# NoteRF_0_3.net
KiCad netlist of a schematic drawn in EAGLE
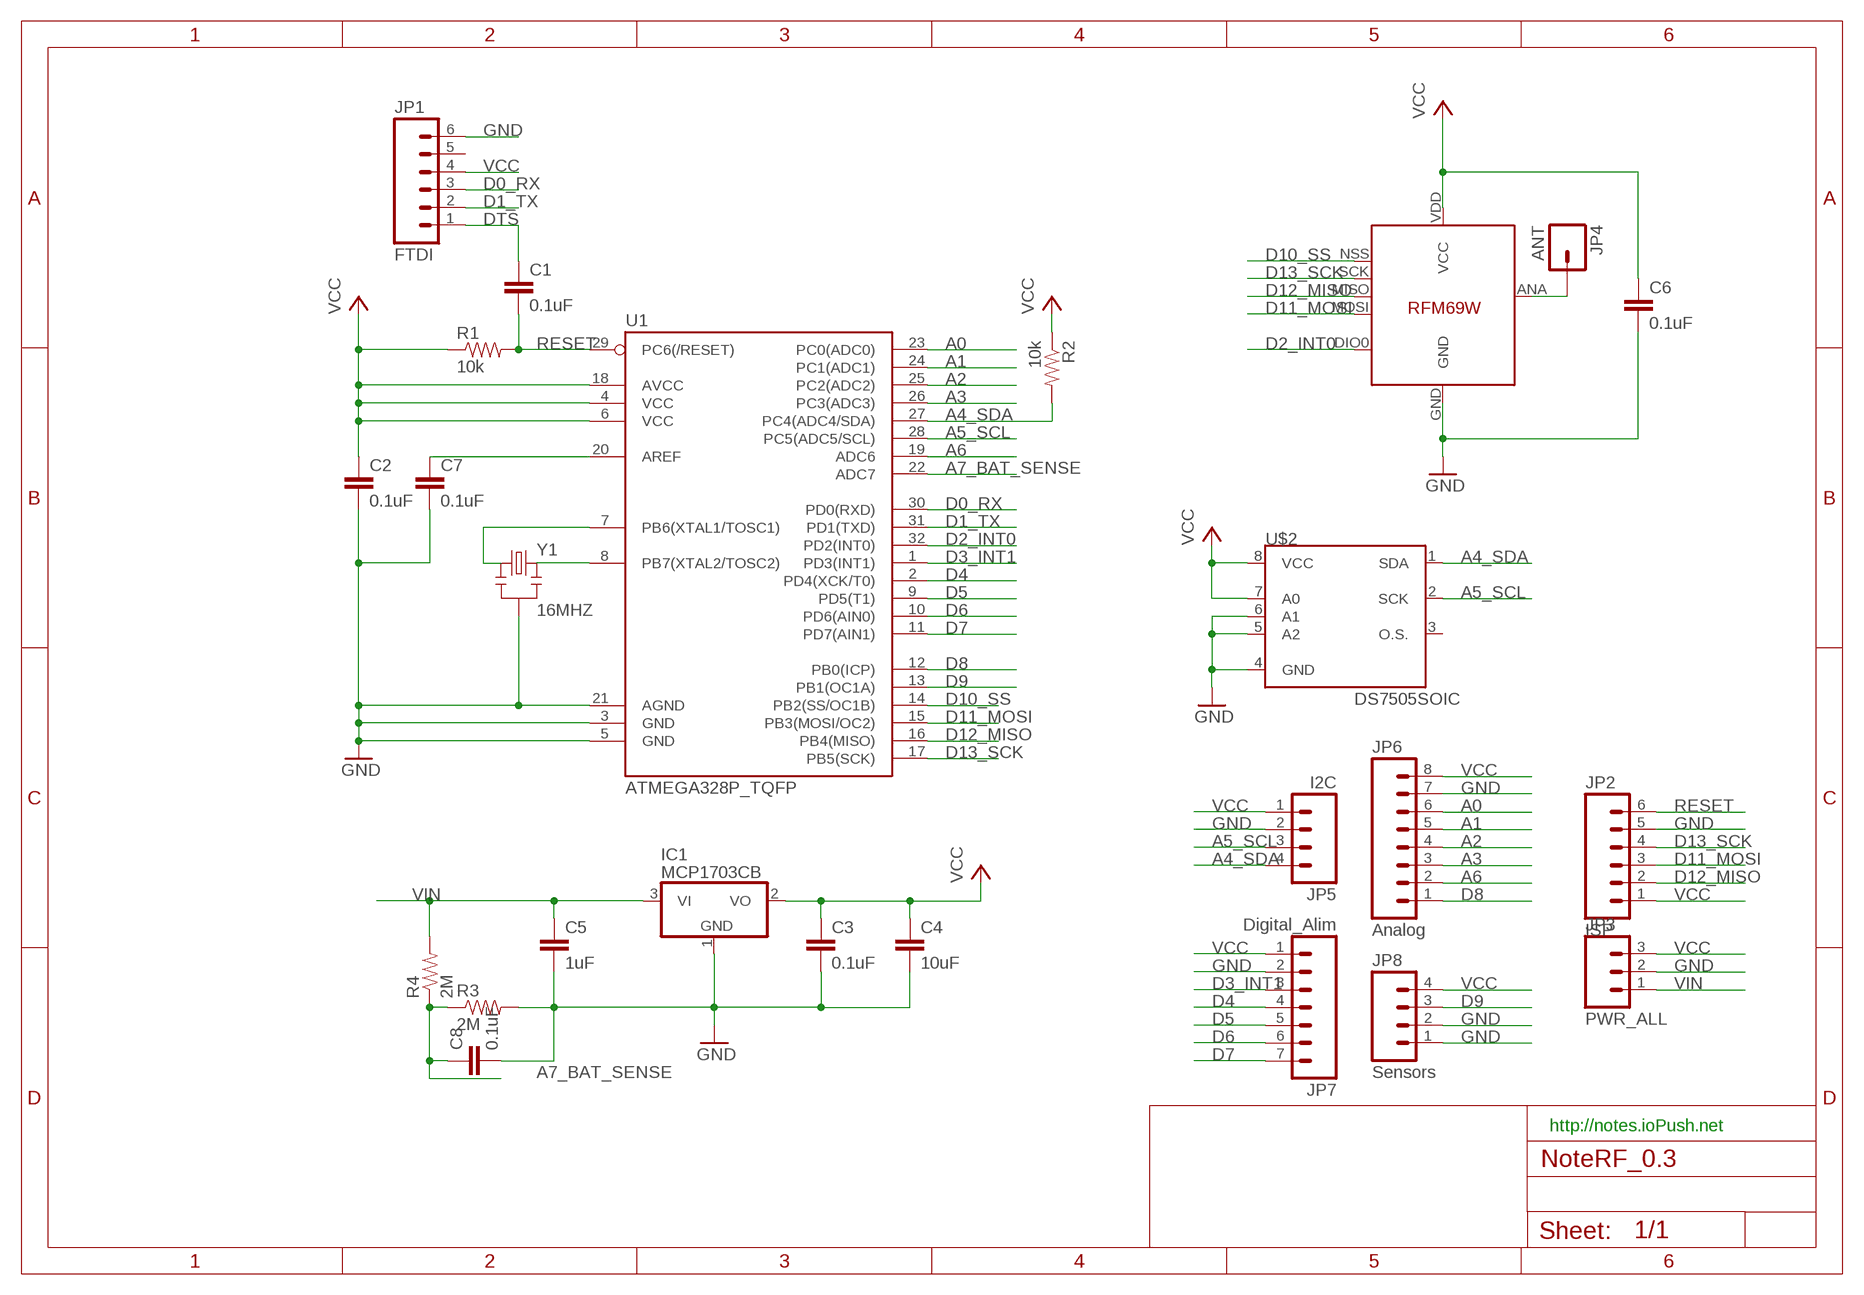
[diagram p0: schematic, sheet 1]

(export (version "E")
  (design (tool "Eeschema 10.0.6"))
  (components
    (comp (ref "C1")
      (value "0.1uF")
      (footprint "eagle-import:0805")
      (libsource (lib "eagle-import") (part "CAP0805"))
    )
    (comp (ref "C2")
      (value "0.1uF")
      (footprint "eagle-import:0805")
      (libsource (lib "eagle-import") (part "CAP0805"))
    )
    (comp (ref "C3")
      (value "0.1uF")
      (footprint "eagle-import:0805")
      (libsource (lib "eagle-import") (part "CAP0805"))
    )
    (comp (ref "C4")
      (value "10uF")
      (footprint "eagle-import:0805")
      (libsource (lib "eagle-import") (part "CAP0805"))
    )
    (comp (ref "C5")
      (value "1uF")
      (footprint "eagle-import:0805")
      (libsource (lib "eagle-import") (part "CAP0805"))
    )
    (comp (ref "C6")
      (value "0.1uF")
      (footprint "eagle-import:0805")
      (libsource (lib "eagle-import") (part "CAP0805"))
    )
    (comp (ref "C7")
      (value "0.1uF")
      (footprint "eagle-import:0805")
      (libsource (lib "eagle-import") (part "CAP0805"))
    )
    (comp (ref "C8")
      (value "0.1uF")
      (footprint "eagle-import:0805")
      (libsource (lib "eagle-import") (part "CAP0805"))
    )
    (comp (ref "IC1")
      (value "MCP1703CB")
      (footprint "eagle-import:SOT23")
      (libsource (lib "eagle-import") (part "MCP1703CB"))
    )
    (comp (ref "JP1")
      (value "FTDI")
      (footprint "eagle-import:1X06_LOCK")
      (libsource (lib "eagle-import") (part "M06LOCK"))
    )
    (comp (ref "JP2")
      (value "ISP")
      (footprint "eagle-import:1X06_LOCK")
      (libsource (lib "eagle-import") (part "M06LOCK"))
    )
    (comp (ref "JP3")
      (value "PWR_ALL")
      (footprint "eagle-import:1X03_LOCK")
      (libsource (lib "eagle-import") (part "M03LOCK"))
    )
    (comp (ref "JP4")
      (value "ANT")
      (footprint "eagle-import:1X01NS-KIT")
      (libsource (lib "eagle-import") (part "M01NOSILK-KIT"))
    )
    (comp (ref "JP5")
      (value "I2C")
      (footprint "eagle-import:1X04_LOCK")
      (libsource (lib "eagle-import") (part "M04LOCK"))
    )
    (comp (ref "JP6")
      (value "Analog")
      (footprint "eagle-import:1X08_LOCK")
      (libsource (lib "eagle-import") (part "M08LOCK"))
    )
    (comp (ref "JP7")
      (value "Digital_Alim")
      (footprint "eagle-import:1X07_LOCK")
      (libsource (lib "eagle-import") (part "M07LOCK"))
    )
    (comp (ref "JP8")
      (value "Sensors")
      (footprint "eagle-import:1X04_LOCK")
      (libsource (lib "eagle-import") (part "M04LOCK"))
    )
    (comp (ref "R1")
      (value "10k")
      (footprint "eagle-import:0805")
      (libsource (lib "eagle-import") (part "RESISTOR0805-RES"))
    )
    (comp (ref "R2")
      (value "10k")
      (footprint "eagle-import:0805")
      (libsource (lib "eagle-import") (part "RESISTOR0805-RES"))
    )
    (comp (ref "R3")
      (value "2M")
      (footprint "eagle-import:0805")
      (libsource (lib "eagle-import") (part "RESISTOR0805-RES"))
    )
    (comp (ref "R4")
      (value "2M")
      (footprint "eagle-import:0805")
      (libsource (lib "eagle-import") (part "RESISTOR0805-RES"))
    )
    (comp (ref "U$1")
      (value "RFM69")
      (footprint "eagle-import:RFM69W-MINPADS")
      (libsource (lib "eagle-import") (part "RFM69"))
    )
    (comp (ref "U$2")
      (value "DS7505SOIC")
      (footprint "eagle-import:SO08")
      (libsource (lib "eagle-import") (part "DS7505SOIC"))
    )
    (comp (ref "U1")
      (value "ATMEGA328P_TQFP")
      (footprint "eagle-import:TQFP32-08")
      (libsource (lib "eagle-import") (part "ATMEGA328P_TQFP"))
    )
    (comp (ref "Y1")
      (value "16MHZ")
      (footprint "eagle-import:RESONATOR-SMD")
      (libsource (lib "eagle-import") (part "RESONATOR16MHZ"))
    )
  )
  (nets
    (net (code "1") (name "/A0") (class "Default")
      (node (ref "JP6") (pin "6") (pinfunction "6_6") (pintype "passive"))
      (node (ref "U1") (pin "23") (pinfunction "PC0(ADC0)_23") (pintype "bidirectional"))
    )
    (net (code "2") (name "/A1") (class "Default")
      (node (ref "JP6") (pin "5") (pinfunction "5_5") (pintype "passive"))
      (node (ref "U1") (pin "24") (pinfunction "PC1(ADC1)_24") (pintype "bidirectional"))
    )
    (net (code "3") (name "/A2") (class "Default")
      (node (ref "JP6") (pin "4") (pinfunction "4_4") (pintype "passive"))
      (node (ref "U1") (pin "25") (pinfunction "PC2(ADC2)_25") (pintype "bidirectional"))
    )
    (net (code "4") (name "/A3") (class "Default")
      (node (ref "JP6") (pin "3") (pinfunction "3_3") (pintype "passive"))
      (node (ref "U1") (pin "26") (pinfunction "PC3(ADC3)_26") (pintype "bidirectional"))
    )
    (net (code "5") (name "/A4_SDA") (class "Default")
      (node (ref "JP5") (pin "4") (pinfunction "4_4") (pintype "passive"))
      (node (ref "R2") (pin "2") (pinfunction "2_2") (pintype "passive"))
      (node (ref "U$2") (pin "1") (pinfunction "SDA_1") (pintype "bidirectional"))
      (node (ref "U1") (pin "27") (pinfunction "PC4(ADC4/SDA)_27") (pintype "bidirectional"))
    )
    (net (code "6") (name "/A5_SCL") (class "Default")
      (node (ref "JP5") (pin "3") (pinfunction "3_3") (pintype "passive"))
      (node (ref "U$2") (pin "2") (pinfunction "SCK_2") (pintype "bidirectional"))
      (node (ref "U1") (pin "28") (pinfunction "PC5(ADC5/SCL)_28") (pintype "bidirectional"))
    )
    (net (code "7") (name "/A6") (class "Default")
      (node (ref "JP6") (pin "2") (pinfunction "2_2") (pintype "passive"))
      (node (ref "U1") (pin "19") (pinfunction "ADC6_19") (pintype "bidirectional"))
    )
    (net (code "8") (name "/A7_BAT_SENSE") (class "Default")
      (node (ref "C8") (pin "1") (pinfunction "1_1") (pintype "passive"))
      (node (ref "R3") (pin "1") (pinfunction "1_1") (pintype "passive"))
      (node (ref "R4") (pin "1") (pinfunction "1_1") (pintype "passive"))
      (node (ref "U1") (pin "22") (pinfunction "ADC7_22") (pintype "bidirectional"))
    )
    (net (code "9") (name "/D0_RX") (class "Default")
      (node (ref "JP1") (pin "3") (pinfunction "3_3") (pintype "passive"))
      (node (ref "U1") (pin "30") (pinfunction "PD0(RXD)_30") (pintype "bidirectional"))
    )
    (net (code "10") (name "/D1_TX") (class "Default")
      (node (ref "JP1") (pin "2") (pinfunction "2_2") (pintype "passive"))
      (node (ref "U1") (pin "31") (pinfunction "PD1(TXD)_31") (pintype "bidirectional"))
    )
    (net (code "11") (name "/D2_INT0") (class "Default")
      (node (ref "U$1") (pin "DIO0") (pinfunction "DIO0_DIO0") (pintype "open_collector"))
      (node (ref "U1") (pin "32") (pinfunction "PD2(INT0)_32") (pintype "bidirectional"))
    )
    (net (code "12") (name "/D3_INT1") (class "Default")
      (node (ref "JP7") (pin "3") (pinfunction "3_3") (pintype "passive"))
      (node (ref "U1") (pin "1") (pinfunction "PD3(INT1)_1") (pintype "bidirectional"))
    )
    (net (code "13") (name "/D4") (class "Default")
      (node (ref "JP7") (pin "4") (pinfunction "4_4") (pintype "passive"))
      (node (ref "U1") (pin "2") (pinfunction "PD4(XCK/T0)_2") (pintype "bidirectional"))
    )
    (net (code "14") (name "/D5") (class "Default")
      (node (ref "JP7") (pin "5") (pinfunction "5_5") (pintype "passive"))
      (node (ref "U1") (pin "9") (pinfunction "PD5(T1)_9") (pintype "bidirectional"))
    )
    (net (code "15") (name "/D6") (class "Default")
      (node (ref "JP7") (pin "6") (pinfunction "6_6") (pintype "passive"))
      (node (ref "U1") (pin "10") (pinfunction "PD6(AIN0)_10") (pintype "bidirectional"))
    )
    (net (code "16") (name "/D7") (class "Default")
      (node (ref "JP7") (pin "7") (pinfunction "7_7") (pintype "passive"))
      (node (ref "U1") (pin "11") (pinfunction "PD7(AIN1)_11") (pintype "bidirectional"))
    )
    (net (code "17") (name "/D8") (class "Default")
      (node (ref "JP6") (pin "1") (pinfunction "1_1") (pintype "passive"))
      (node (ref "U1") (pin "12") (pinfunction "PB0(ICP)_12") (pintype "bidirectional"))
    )
    (net (code "18") (name "/D9") (class "Default")
      (node (ref "JP8") (pin "3") (pinfunction "3_3") (pintype "passive"))
      (node (ref "U1") (pin "13") (pinfunction "PB1(OC1A)_13") (pintype "bidirectional"))
    )
    (net (code "19") (name "/D10_SS") (class "Default")
      (node (ref "U$1") (pin "NSS") (pinfunction "SEL_NSS") (pintype "input"))
      (node (ref "U1") (pin "14") (pinfunction "PB2(SS/OC1B)_14") (pintype "bidirectional"))
    )
    (net (code "20") (name "/D11_MOSI") (class "Default")
      (node (ref "JP2") (pin "3") (pinfunction "3_3") (pintype "passive"))
      (node (ref "U$1") (pin "MOSI") (pinfunction "MOSI_MOSI") (pintype "output"))
      (node (ref "U1") (pin "15") (pinfunction "PB3(MOSI/OC2)_15") (pintype "bidirectional"))
    )
    (net (code "21") (name "/D12_MISO") (class "Default")
      (node (ref "JP2") (pin "2") (pinfunction "2_2") (pintype "passive"))
      (node (ref "U$1") (pin "MISO") (pinfunction "MISO_MISO") (pintype "input"))
      (node (ref "U1") (pin "16") (pinfunction "PB4(MISO)_16") (pintype "bidirectional"))
    )
    (net (code "22") (name "/D13_SCK") (class "Default")
      (node (ref "JP2") (pin "4") (pinfunction "4_4") (pintype "passive"))
      (node (ref "U$1") (pin "SCK") (pinfunction "SCK_SCK") (pintype "input"))
      (node (ref "U1") (pin "17") (pinfunction "PB5(SCK)_17") (pintype "bidirectional"))
    )
    (net (code "23") (name "/DTS") (class "Default")
      (node (ref "C1") (pin "1") (pinfunction "1_1") (pintype "passive"))
      (node (ref "JP1") (pin "1") (pinfunction "1_1") (pintype "passive"))
    )
    (net (code "24") (name "/RESET") (class "Default")
      (node (ref "C1") (pin "2") (pinfunction "2_2") (pintype "passive"))
      (node (ref "JP2") (pin "6") (pinfunction "6_6") (pintype "passive"))
      (node (ref "R1") (pin "2") (pinfunction "2_2") (pintype "passive"))
      (node (ref "U1") (pin "29") (pinfunction "PC6(/RESET)_29") (pintype "bidirectional"))
    )
    (net (code "25") (name "/VIN") (class "Default")
      (node (ref "C5") (pin "1") (pinfunction "1_1") (pintype "passive"))
      (node (ref "IC1") (pin "3") (pinfunction "VI_3") (pintype "input"))
      (node (ref "JP3") (pin "1") (pinfunction "1_1") (pintype "passive"))
      (node (ref "R4") (pin "2") (pinfunction "2_2") (pintype "passive"))
    )
    (net (code "26") (name "GND") (class "Default")
      (node (ref "C2") (pin "2") (pinfunction "2_2") (pintype "passive"))
      (node (ref "C3") (pin "2") (pinfunction "2_2") (pintype "passive"))
      (node (ref "C4") (pin "2") (pinfunction "2_2") (pintype "passive"))
      (node (ref "C5") (pin "2") (pinfunction "2_2") (pintype "passive"))
      (node (ref "C6") (pin "2") (pinfunction "2_2") (pintype "passive"))
      (node (ref "C7") (pin "2") (pinfunction "2_2") (pintype "passive"))
      (node (ref "C8") (pin "2") (pinfunction "2_2") (pintype "passive"))
      (node (ref "IC1") (pin "1") (pinfunction "GND_1") (pintype "passive"))
      (node (ref "JP1") (pin "6") (pinfunction "6_6") (pintype "passive"))
      (node (ref "JP2") (pin "5") (pinfunction "5_5") (pintype "passive"))
      (node (ref "JP3") (pin "2") (pinfunction "2_2") (pintype "passive"))
      (node (ref "JP5") (pin "2") (pinfunction "2_2") (pintype "passive"))
      (node (ref "JP6") (pin "7") (pinfunction "7_7") (pintype "passive"))
      (node (ref "JP7") (pin "2") (pinfunction "2_2") (pintype "passive"))
      (node (ref "JP8") (pin "1") (pinfunction "1_1") (pintype "passive"))
      (node (ref "JP8") (pin "2") (pinfunction "2_2") (pintype "passive"))
      (node (ref "R3") (pin "2") (pinfunction "2_2") (pintype "passive"))
      (node (ref "U$1") (pin "GND") (pinfunction "GND_GND") (pintype "power_in"))
      (node (ref "U$2") (pin "4") (pinfunction "GND_4") (pintype "bidirectional"))
      (node (ref "U$2") (pin "5") (pinfunction "A2_5") (pintype "bidirectional"))
      (node (ref "U$2") (pin "6") (pinfunction "A1_6") (pintype "bidirectional"))
      (node (ref "U1") (pin "21") (pinfunction "AGND_21") (pintype "bidirectional"))
      (node (ref "U1") (pin "3") (pinfunction "GND_3") (pintype "bidirectional"))
      (node (ref "U1") (pin "5") (pinfunction "GND_5") (pintype "bidirectional"))
      (node (ref "Y1") (pin "2") (pinfunction "2_2") (pintype "passive"))
    )
    (net (code "27") (name "Net-(U$1-ANT)") (class "Default")
      (node (ref "JP4") (pin "1") (pinfunction "1_1") (pintype "passive"))
      (node (ref "U$1") (pin "ANA") (pinfunction "ANT_ANA") (pintype "passive"))
    )
    (net (code "28") (name "Net-(U1-AREF)") (class "Default")
      (node (ref "C7") (pin "1") (pinfunction "1_1") (pintype "passive"))
      (node (ref "U1") (pin "20") (pinfunction "AREF_20") (pintype "bidirectional"))
    )
    (net (code "29") (name "Net-(U1-PB6(XTAL1{slash}TOSC1))") (class "Default")
      (node (ref "U1") (pin "7") (pinfunction "PB6(XTAL1/TOSC1)_7") (pintype "bidirectional"))
      (node (ref "Y1") (pin "1") (pinfunction "1_1") (pintype "passive"))
    )
    (net (code "30") (name "Net-(U1-PB7(XTAL2{slash}TOSC2))") (class "Default")
      (node (ref "U1") (pin "8") (pinfunction "PB7(XTAL2/TOSC2)_8") (pintype "bidirectional"))
      (node (ref "Y1") (pin "3") (pinfunction "3_3") (pintype "passive"))
    )
    (net (code "31") (name "VCC") (class "Default")
      (node (ref "C2") (pin "1") (pinfunction "1_1") (pintype "passive"))
      (node (ref "C3") (pin "1") (pinfunction "1_1") (pintype "passive"))
      (node (ref "C4") (pin "1") (pinfunction "1_1") (pintype "passive"))
      (node (ref "C6") (pin "1") (pinfunction "1_1") (pintype "passive"))
      (node (ref "IC1") (pin "2") (pinfunction "VO_2") (pintype "passive"))
      (node (ref "JP1") (pin "4") (pinfunction "4_4") (pintype "passive"))
      (node (ref "JP2") (pin "1") (pinfunction "1_1") (pintype "passive"))
      (node (ref "JP3") (pin "3") (pinfunction "3_3") (pintype "passive"))
      (node (ref "JP5") (pin "1") (pinfunction "1_1") (pintype "passive"))
      (node (ref "JP6") (pin "8") (pinfunction "8_8") (pintype "passive"))
      (node (ref "JP7") (pin "1") (pinfunction "1_1") (pintype "passive"))
      (node (ref "JP8") (pin "4") (pinfunction "4_4") (pintype "passive"))
      (node (ref "R1") (pin "1") (pinfunction "1_1") (pintype "passive"))
      (node (ref "R2") (pin "1") (pinfunction "1_1") (pintype "passive"))
      (node (ref "U$1") (pin "VDD") (pinfunction "VCC_VDD") (pintype "power_in"))
      (node (ref "U$2") (pin "7") (pinfunction "A0_7") (pintype "bidirectional"))
      (node (ref "U$2") (pin "8") (pinfunction "VCC_8") (pintype "bidirectional"))
      (node (ref "U1") (pin "18") (pinfunction "AVCC_18") (pintype "bidirectional"))
      (node (ref "U1") (pin "4") (pinfunction "VCC_4") (pintype "bidirectional"))
      (node (ref "U1") (pin "6") (pinfunction "VCC_6") (pintype "bidirectional"))
    )
    (net (code "32") (name "unconnected-(JP1-Pad5)") (class "Default")
      (node (ref "JP1") (pin "5") (pinfunction "5_5") (pintype "passive"))
    )
    (net (code "33") (name "unconnected-(U$2-O.S.-Pad3)") (class "Default")
      (node (ref "U$2") (pin "3") (pinfunction "O.S._3") (pintype "bidirectional"))
    )
  )
)
